# RGBNDR.net
KiCad netlist of a schematic drawn in EAGLE
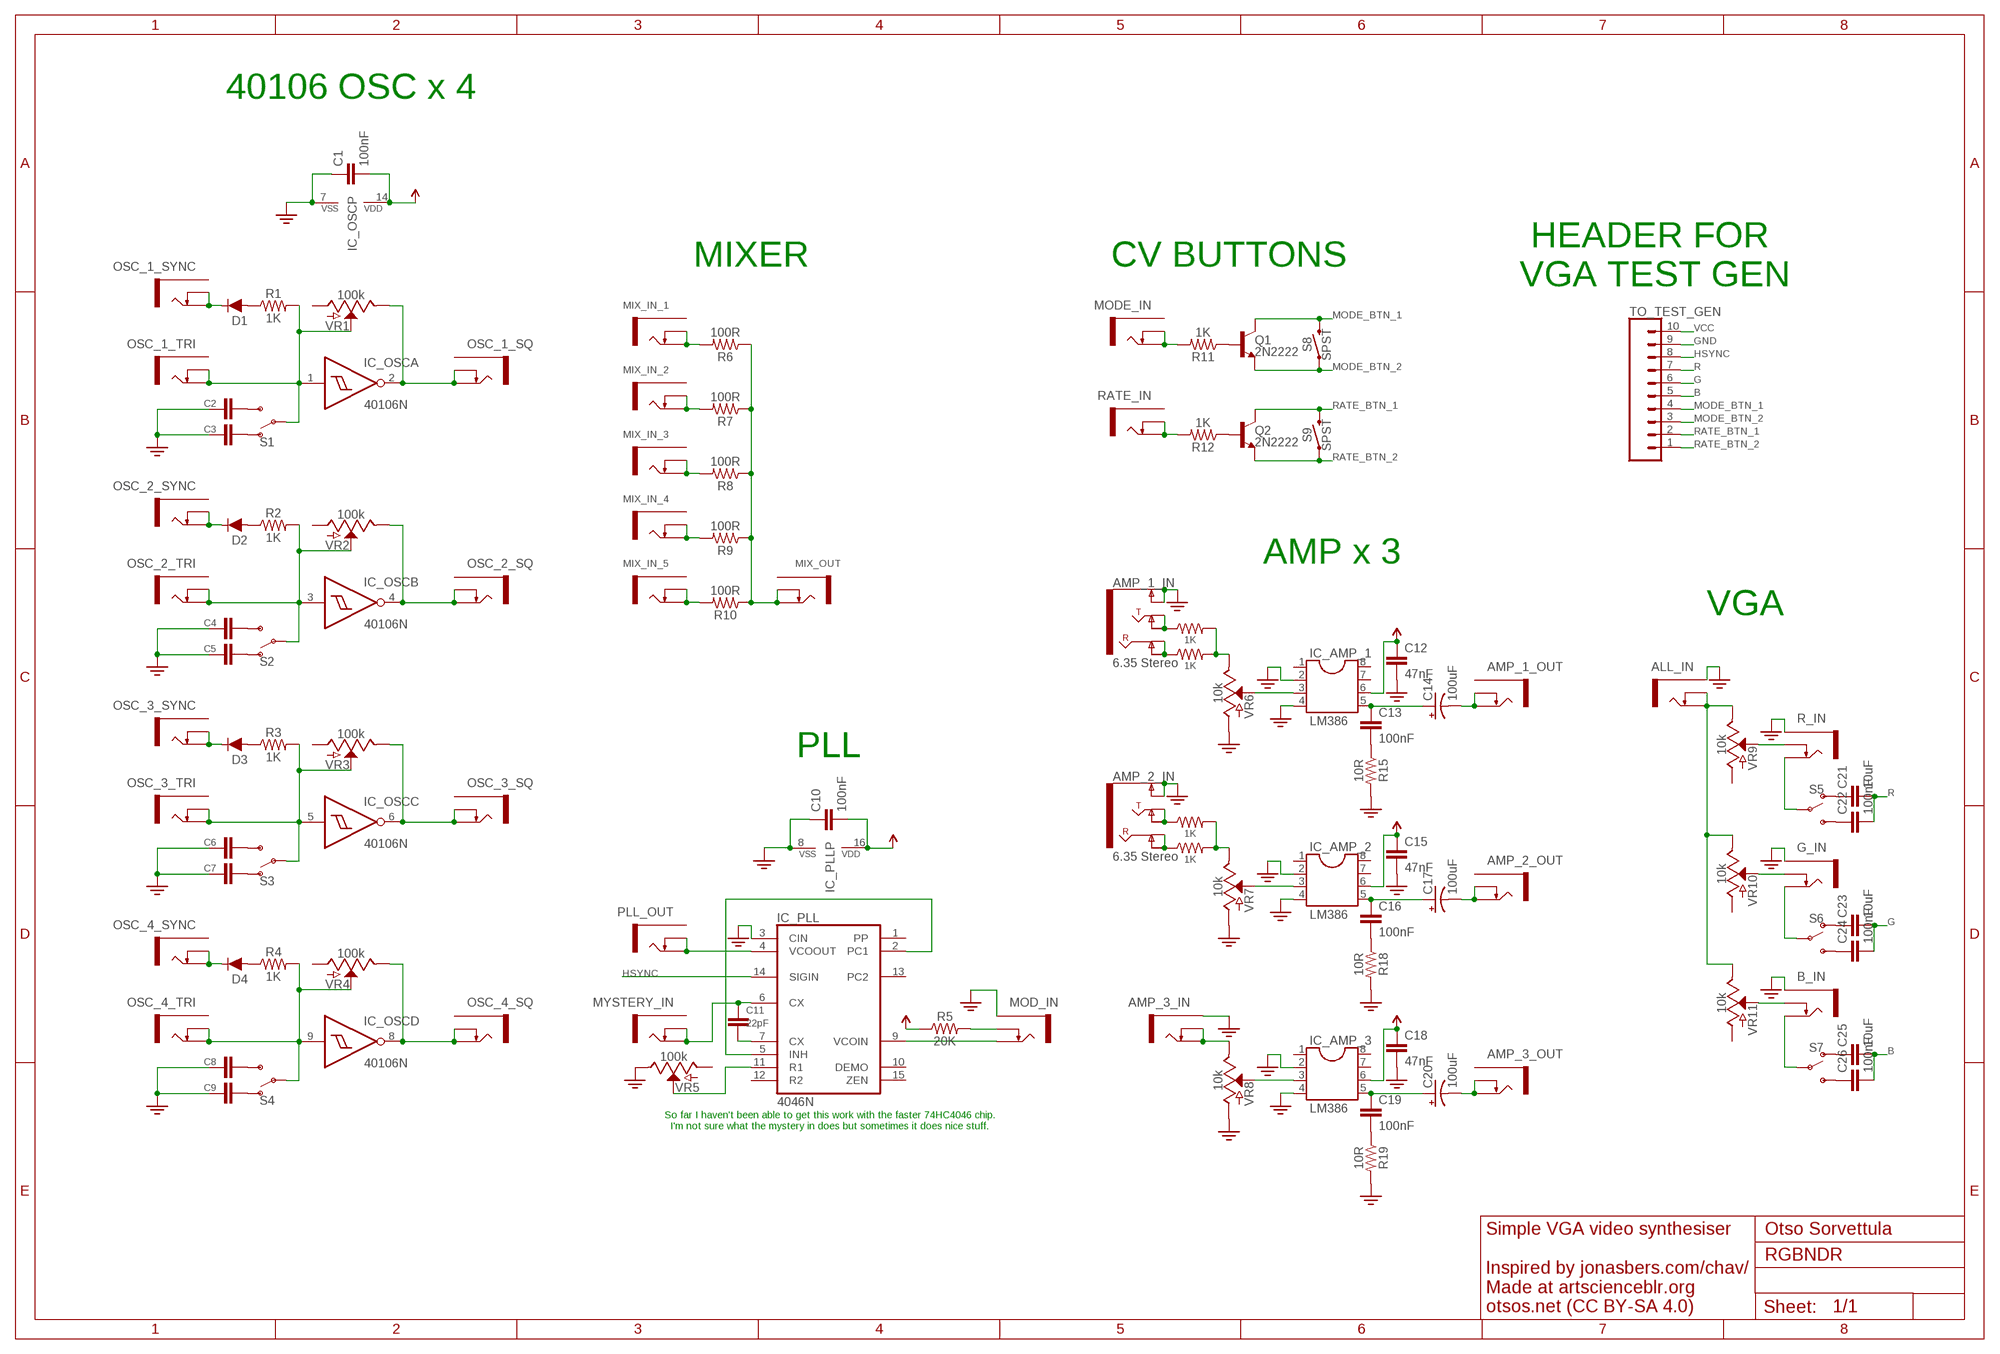
[diagram p0: schematic, sheet 1]

(export (version "E")
  (design (tool "Eeschema 10.0.6"))
  (components
    (comp (ref "ALL_IN")
      (value "WQP-PJ301M-12_JACK")
      (footprint "eagle-import:WQP-PJ301M-12_JACK")
      (libsource (lib "eagle-import") (part "WQP-PJ301M-12_JACK"))
    )
    (comp (ref "AMP_1_IN")
      (value "6.35 Stereo")
      (footprint "eagle-import:AUDIO_JACK_0.25__TRS_PTH_RA")
      (libsource (lib "eagle-import") (part "AUDIO_JACK_TRS_0.25{dblquote}_PTH_RA"))
    )
    (comp (ref "AMP_1_OUT")
      (value "WQP-PJ301M-12_JACK")
      (footprint "eagle-import:WQP-PJ301M-12_JACK")
      (libsource (lib "eagle-import") (part "WQP-PJ301M-12_JACK"))
    )
    (comp (ref "AMP_2_IN")
      (value "6.35 Stereo")
      (footprint "eagle-import:AUDIO_JACK_0.25__TRS_PTH_RA")
      (libsource (lib "eagle-import") (part "AUDIO_JACK_TRS_0.25{dblquote}_PTH_RA"))
    )
    (comp (ref "AMP_2_OUT")
      (value "WQP-PJ301M-12_JACK")
      (footprint "eagle-import:WQP-PJ301M-12_JACK")
      (libsource (lib "eagle-import") (part "WQP-PJ301M-12_JACK"))
    )
    (comp (ref "AMP_3_IN")
      (value "WQP-PJ301M-12_JACK")
      (footprint "eagle-import:WQP-PJ301M-12_JACK")
      (libsource (lib "eagle-import") (part "WQP-PJ301M-12_JACK"))
    )
    (comp (ref "AMP_3_OUT")
      (value "WQP-PJ301M-12_JACK")
      (footprint "eagle-import:WQP-PJ301M-12_JACK")
      (libsource (lib "eagle-import") (part "WQP-PJ301M-12_JACK"))
    )
    (comp (ref "B_IN")
      (value "WQP-PJ301M-12_JACK")
      (footprint "eagle-import:WQP-PJ301M-12_JACK")
      (libsource (lib "eagle-import") (part "WQP-PJ301M-12_JACK"))
    )
    (comp (ref "C1")
      (value "100nF")
      (footprint "eagle-import:CAP-PTH-SMALL-KIT")
      (libsource (lib "eagle-import") (part "0.1UF-KIT-EZ-50V-20%"))
    )
    (comp (ref "C2")
      (value "0.1UF-KIT-EZ-50V-20%")
      (footprint "eagle-import:CAP-PTH-SMALL-KIT")
      (libsource (lib "eagle-import") (part "0.1UF-KIT-EZ-50V-20%"))
    )
    (comp (ref "C3")
      (value "0.1UF-KIT-EZ-50V-20%")
      (footprint "eagle-import:CAP-PTH-SMALL-KIT")
      (libsource (lib "eagle-import") (part "0.1UF-KIT-EZ-50V-20%"))
    )
    (comp (ref "C4")
      (value "0.1UF-KIT-EZ-50V-20%")
      (footprint "eagle-import:CAP-PTH-SMALL-KIT")
      (libsource (lib "eagle-import") (part "0.1UF-KIT-EZ-50V-20%"))
    )
    (comp (ref "C5")
      (value "0.1UF-KIT-EZ-50V-20%")
      (footprint "eagle-import:CAP-PTH-SMALL-KIT")
      (libsource (lib "eagle-import") (part "0.1UF-KIT-EZ-50V-20%"))
    )
    (comp (ref "C6")
      (value "0.1UF-KIT-EZ-50V-20%")
      (footprint "eagle-import:CAP-PTH-SMALL-KIT")
      (libsource (lib "eagle-import") (part "0.1UF-KIT-EZ-50V-20%"))
    )
    (comp (ref "C7")
      (value "0.1UF-KIT-EZ-50V-20%")
      (footprint "eagle-import:CAP-PTH-SMALL-KIT")
      (libsource (lib "eagle-import") (part "0.1UF-KIT-EZ-50V-20%"))
    )
    (comp (ref "C8")
      (value "0.1UF-KIT-EZ-50V-20%")
      (footprint "eagle-import:CAP-PTH-SMALL-KIT")
      (libsource (lib "eagle-import") (part "0.1UF-KIT-EZ-50V-20%"))
    )
    (comp (ref "C9")
      (value "0.1UF-KIT-EZ-50V-20%")
      (footprint "eagle-import:CAP-PTH-SMALL-KIT")
      (libsource (lib "eagle-import") (part "0.1UF-KIT-EZ-50V-20%"))
    )
    (comp (ref "C10")
      (value "100nF")
      (footprint "eagle-import:CAP-PTH-SMALL-KIT")
      (libsource (lib "eagle-import") (part "0.1UF-KIT-EZ-50V-20%"))
    )
    (comp (ref "C11")
      (value "22pF")
      (footprint "eagle-import:CAP-PTH-2.54")
      (libsource (lib "eagle-import") (part "22PF-PTH-2.54MM-200V-5%"))
    )
    (comp (ref "C12")
      (value "47nF")
      (footprint "eagle-import:CAP-PTH-SMALL-KIT")
      (libsource (lib "eagle-import") (part "0.1UF-KIT-EZ-50V-20%"))
    )
    (comp (ref "C13")
      (value "100nF")
      (footprint "eagle-import:CAP-PTH-SMALL-KIT")
      (libsource (lib "eagle-import") (part "0.1UF-KIT-EZ-50V-20%"))
    )
    (comp (ref "C14")
      (value "100uF")
      (footprint "eagle-import:CPOL-RADIAL-2.5MM-6.5MM")
      (libsource (lib "eagle-import") (part "100UF-POLAR-RADIAL-2.5MM-25V-20%"))
    )
    (comp (ref "C15")
      (value "47nF")
      (footprint "eagle-import:CAP-PTH-SMALL-KIT")
      (libsource (lib "eagle-import") (part "0.1UF-KIT-EZ-50V-20%"))
    )
    (comp (ref "C16")
      (value "100nF")
      (footprint "eagle-import:CAP-PTH-SMALL-KIT")
      (libsource (lib "eagle-import") (part "0.1UF-KIT-EZ-50V-20%"))
    )
    (comp (ref "C17")
      (value "100uF")
      (footprint "eagle-import:CPOL-RADIAL-2.5MM-6.5MM")
      (libsource (lib "eagle-import") (part "100UF-POLAR-RADIAL-2.5MM-25V-20%"))
    )
    (comp (ref "C18")
      (value "47nF")
      (footprint "eagle-import:CAP-PTH-SMALL-KIT")
      (libsource (lib "eagle-import") (part "0.1UF-KIT-EZ-50V-20%"))
    )
    (comp (ref "C19")
      (value "100nF")
      (footprint "eagle-import:CAP-PTH-SMALL-KIT")
      (libsource (lib "eagle-import") (part "0.1UF-KIT-EZ-50V-20%"))
    )
    (comp (ref "C20")
      (value "100uF")
      (footprint "eagle-import:CPOL-RADIAL-2.5MM-6.5MM")
      (libsource (lib "eagle-import") (part "100UF-POLAR-RADIAL-2.5MM-25V-20%"))
    )
    (comp (ref "C21")
      (value "10uF")
      (footprint "eagle-import:CAP-PTH-SMALL-KIT")
      (libsource (lib "eagle-import") (part "0.1UF-KIT-EZ-50V-20%"))
    )
    (comp (ref "C22")
      (value "100nF")
      (footprint "eagle-import:CAP-PTH-SMALL-KIT")
      (libsource (lib "eagle-import") (part "0.1UF-KIT-EZ-50V-20%"))
    )
    (comp (ref "C23")
      (value "10uF")
      (footprint "eagle-import:CAP-PTH-SMALL-KIT")
      (libsource (lib "eagle-import") (part "0.1UF-KIT-EZ-50V-20%"))
    )
    (comp (ref "C24")
      (value "100nF")
      (footprint "eagle-import:CAP-PTH-SMALL-KIT")
      (libsource (lib "eagle-import") (part "0.1UF-KIT-EZ-50V-20%"))
    )
    (comp (ref "C25")
      (value "10uF")
      (footprint "eagle-import:CAP-PTH-SMALL-KIT")
      (libsource (lib "eagle-import") (part "0.1UF-KIT-EZ-50V-20%"))
    )
    (comp (ref "C26")
      (value "100nF")
      (footprint "eagle-import:CAP-PTH-SMALL-KIT")
      (libsource (lib "eagle-import") (part "0.1UF-KIT-EZ-50V-20%"))
    )
    (comp (ref "D1")
      (value "DIODE-1N4148")
      (footprint "eagle-import:DIODE-1N4148")
      (libsource (lib "eagle-import") (part "DIODE-1N4148"))
    )
    (comp (ref "D2")
      (value "DIODE-1N4148")
      (footprint "eagle-import:DIODE-1N4148")
      (libsource (lib "eagle-import") (part "DIODE-1N4148"))
    )
    (comp (ref "D3")
      (value "DIODE-1N4148")
      (footprint "eagle-import:DIODE-1N4148")
      (libsource (lib "eagle-import") (part "DIODE-1N4148"))
    )
    (comp (ref "D4")
      (value "DIODE-1N4148")
      (footprint "eagle-import:DIODE-1N4148")
      (libsource (lib "eagle-import") (part "DIODE-1N4148"))
    )
    (comp (ref "G_IN")
      (value "WQP-PJ301M-12_JACK")
      (footprint "eagle-import:WQP-PJ301M-12_JACK")
      (libsource (lib "eagle-import") (part "WQP-PJ301M-12_JACK"))
    )
    (comp (ref "IC_AMP_1")
      (value "LM386")
      (footprint "eagle-import:DIL08")
      (libsource (lib "eagle-import") (part "DIL8"))
    )
    (comp (ref "IC_AMP_2")
      (value "LM386")
      (footprint "eagle-import:DIL08")
      (libsource (lib "eagle-import") (part "DIL8"))
    )
    (comp (ref "IC_AMP_3")
      (value "LM386")
      (footprint "eagle-import:DIL08")
      (libsource (lib "eagle-import") (part "DIL8"))
    )
    (comp (ref "IC_OSC")
      (value "40106N")
      (footprint "eagle-import:DIL14")
      (libsource (lib "eagle-import") (part "40106N"))
    )
    (comp (ref "IC_PLL")
      (value "4046N")
      (footprint "eagle-import:DIL16")
      (libsource (lib "eagle-import") (part "4046N"))
    )
    (comp (ref "MIX_IN_1")
      (value "WQP-PJ301M-12_JACK")
      (footprint "eagle-import:WQP-PJ301M-12_JACK")
      (libsource (lib "eagle-import") (part "WQP-PJ301M-12_JACK"))
    )
    (comp (ref "MIX_IN_2")
      (value "WQP-PJ301M-12_JACK")
      (footprint "eagle-import:WQP-PJ301M-12_JACK")
      (libsource (lib "eagle-import") (part "WQP-PJ301M-12_JACK"))
    )
    (comp (ref "MIX_IN_3")
      (value "WQP-PJ301M-12_JACK")
      (footprint "eagle-import:WQP-PJ301M-12_JACK")
      (libsource (lib "eagle-import") (part "WQP-PJ301M-12_JACK"))
    )
    (comp (ref "MIX_IN_4")
      (value "WQP-PJ301M-12_JACK")
      (footprint "eagle-import:WQP-PJ301M-12_JACK")
      (libsource (lib "eagle-import") (part "WQP-PJ301M-12_JACK"))
    )
    (comp (ref "MIX_IN_5")
      (value "WQP-PJ301M-12_JACK")
      (footprint "eagle-import:WQP-PJ301M-12_JACK")
      (libsource (lib "eagle-import") (part "WQP-PJ301M-12_JACK"))
    )
    (comp (ref "MIX_OUT")
      (value "WQP-PJ301M-12_JACK")
      (footprint "eagle-import:WQP-PJ301M-12_JACK")
      (libsource (lib "eagle-import") (part "WQP-PJ301M-12_JACK"))
    )
    (comp (ref "MODE_IN")
      (value "WQP-PJ301M-12_JACK")
      (footprint "eagle-import:WQP-PJ301M-12_JACK")
      (libsource (lib "eagle-import") (part "WQP-PJ301M-12_JACK"))
    )
    (comp (ref "MOD_IN")
      (value "WQP-PJ301M-12_JACK")
      (footprint "eagle-import:WQP-PJ301M-12_JACK")
      (libsource (lib "eagle-import") (part "WQP-PJ301M-12_JACK"))
    )
    (comp (ref "MYSTERY_IN")
      (value "WQP-PJ301M-12_JACK")
      (footprint "eagle-import:WQP-PJ301M-12_JACK")
      (libsource (lib "eagle-import") (part "WQP-PJ301M-12_JACK"))
    )
    (comp (ref "OSC_1_SQ")
      (value "WQP-PJ301M-12_JACK")
      (footprint "eagle-import:WQP-PJ301M-12_JACK")
      (libsource (lib "eagle-import") (part "WQP-PJ301M-12_JACK"))
    )
    (comp (ref "OSC_1_SYNC")
      (value "WQP-PJ301M-12_JACK")
      (footprint "eagle-import:WQP-PJ301M-12_JACK")
      (libsource (lib "eagle-import") (part "WQP-PJ301M-12_JACK"))
    )
    (comp (ref "OSC_1_TRI")
      (value "WQP-PJ301M-12_JACK")
      (footprint "eagle-import:WQP-PJ301M-12_JACK")
      (libsource (lib "eagle-import") (part "WQP-PJ301M-12_JACK"))
    )
    (comp (ref "OSC_2_SQ")
      (value "WQP-PJ301M-12_JACK")
      (footprint "eagle-import:WQP-PJ301M-12_JACK")
      (libsource (lib "eagle-import") (part "WQP-PJ301M-12_JACK"))
    )
    (comp (ref "OSC_2_SYNC")
      (value "WQP-PJ301M-12_JACK")
      (footprint "eagle-import:WQP-PJ301M-12_JACK")
      (libsource (lib "eagle-import") (part "WQP-PJ301M-12_JACK"))
    )
    (comp (ref "OSC_2_TRI")
      (value "WQP-PJ301M-12_JACK")
      (footprint "eagle-import:WQP-PJ301M-12_JACK")
      (libsource (lib "eagle-import") (part "WQP-PJ301M-12_JACK"))
    )
    (comp (ref "OSC_3_SQ")
      (value "WQP-PJ301M-12_JACK")
      (footprint "eagle-import:WQP-PJ301M-12_JACK")
      (libsource (lib "eagle-import") (part "WQP-PJ301M-12_JACK"))
    )
    (comp (ref "OSC_3_SYNC")
      (value "WQP-PJ301M-12_JACK")
      (footprint "eagle-import:WQP-PJ301M-12_JACK")
      (libsource (lib "eagle-import") (part "WQP-PJ301M-12_JACK"))
    )
    (comp (ref "OSC_3_TRI")
      (value "WQP-PJ301M-12_JACK")
      (footprint "eagle-import:WQP-PJ301M-12_JACK")
      (libsource (lib "eagle-import") (part "WQP-PJ301M-12_JACK"))
    )
    (comp (ref "OSC_4_SQ")
      (value "WQP-PJ301M-12_JACK")
      (footprint "eagle-import:WQP-PJ301M-12_JACK")
      (libsource (lib "eagle-import") (part "WQP-PJ301M-12_JACK"))
    )
    (comp (ref "OSC_4_SYNC")
      (value "WQP-PJ301M-12_JACK")
      (footprint "eagle-import:WQP-PJ301M-12_JACK")
      (libsource (lib "eagle-import") (part "WQP-PJ301M-12_JACK"))
    )
    (comp (ref "OSC_4_TRI")
      (value "WQP-PJ301M-12_JACK")
      (footprint "eagle-import:WQP-PJ301M-12_JACK")
      (libsource (lib "eagle-import") (part "WQP-PJ301M-12_JACK"))
    )
    (comp (ref "PLL_OUT")
      (value "WQP-PJ301M-12_JACK")
      (footprint "eagle-import:WQP-PJ301M-12_JACK")
      (libsource (lib "eagle-import") (part "WQP-PJ301M-12_JACK"))
    )
    (comp (ref "Q1")
      (value "2N2222")
      (footprint "eagle-import:TO-92")
      (libsource (lib "eagle-import") (part "TRANS_NPN-P2N2222A"))
    )
    (comp (ref "Q2")
      (value "2N2222")
      (footprint "eagle-import:TO-92")
      (libsource (lib "eagle-import") (part "TRANS_NPN-P2N2222A"))
    )
    (comp (ref "R1")
      (value "1K")
      (footprint "eagle-import:AXIAL-0.3")
      (libsource (lib "eagle-import") (part "10KOHM-HORIZ-1/4W-5%"))
    )
    (comp (ref "R2")
      (value "1K")
      (footprint "eagle-import:AXIAL-0.3")
      (libsource (lib "eagle-import") (part "10KOHM-HORIZ-1/4W-5%"))
    )
    (comp (ref "R3")
      (value "1K")
      (footprint "eagle-import:AXIAL-0.3")
      (libsource (lib "eagle-import") (part "10KOHM-HORIZ-1/4W-5%"))
    )
    (comp (ref "R4")
      (value "1K")
      (footprint "eagle-import:AXIAL-0.3")
      (libsource (lib "eagle-import") (part "10KOHM-HORIZ-1/4W-5%"))
    )
    (comp (ref "R5")
      (value "20K")
      (footprint "eagle-import:AXIAL-0.3")
      (libsource (lib "eagle-import") (part "10KOHM-HORIZ-1/4W-5%"))
    )
    (comp (ref "R6")
      (value "100R")
      (footprint "eagle-import:AXIAL-0.3")
      (libsource (lib "eagle-import") (part "10KOHM-HORIZ-1/4W-5%"))
    )
    (comp (ref "R7")
      (value "100R")
      (footprint "eagle-import:AXIAL-0.3")
      (libsource (lib "eagle-import") (part "10KOHM-HORIZ-1/4W-5%"))
    )
    (comp (ref "R8")
      (value "100R")
      (footprint "eagle-import:AXIAL-0.3")
      (libsource (lib "eagle-import") (part "10KOHM-HORIZ-1/4W-5%"))
    )
    (comp (ref "R9")
      (value "100R")
      (footprint "eagle-import:AXIAL-0.3")
      (libsource (lib "eagle-import") (part "10KOHM-HORIZ-1/4W-5%"))
    )
    (comp (ref "R10")
      (value "100R")
      (footprint "eagle-import:AXIAL-0.3")
      (libsource (lib "eagle-import") (part "10KOHM-HORIZ-1/4W-5%"))
    )
    (comp (ref "R11")
      (value "1K")
      (footprint "eagle-import:AXIAL-0.3")
      (libsource (lib "eagle-import") (part "10KOHM-HORIZ-1/4W-5%"))
    )
    (comp (ref "R12")
      (value "1K")
      (footprint "eagle-import:AXIAL-0.3")
      (libsource (lib "eagle-import") (part "10KOHM-HORIZ-1/4W-5%"))
    )
    (comp (ref "R13")
      (value "1K")
      (footprint "eagle-import:AXIAL-0.3")
      (libsource (lib "eagle-import") (part "10KOHM-HORIZ-1/4W-5%"))
    )
    (comp (ref "R14")
      (value "1K")
      (footprint "eagle-import:AXIAL-0.3")
      (libsource (lib "eagle-import") (part "10KOHM-HORIZ-1/4W-5%"))
    )
    (comp (ref "R15")
      (value "10R")
      (footprint "eagle-import:AXIAL-0.3")
      (libsource (lib "eagle-import") (part "10KOHM-HORIZ-1/4W-5%"))
    )
    (comp (ref "R16")
      (value "1K")
      (footprint "eagle-import:AXIAL-0.3")
      (libsource (lib "eagle-import") (part "10KOHM-HORIZ-1/4W-5%"))
    )
    (comp (ref "R17")
      (value "1K")
      (footprint "eagle-import:AXIAL-0.3")
      (libsource (lib "eagle-import") (part "10KOHM-HORIZ-1/4W-5%"))
    )
    (comp (ref "R18")
      (value "10R")
      (footprint "eagle-import:AXIAL-0.3")
      (libsource (lib "eagle-import") (part "10KOHM-HORIZ-1/4W-5%"))
    )
    (comp (ref "R19")
      (value "10R")
      (footprint "eagle-import:AXIAL-0.3")
      (libsource (lib "eagle-import") (part "10KOHM-HORIZ-1/4W-5%"))
    )
    (comp (ref "RATE_IN")
      (value "WQP-PJ301M-12_JACK")
      (footprint "eagle-import:WQP-PJ301M-12_JACK")
      (libsource (lib "eagle-import") (part "WQP-PJ301M-12_JACK"))
    )
    (comp (ref "R_IN")
      (value "WQP-PJ301M-12_JACK")
      (footprint "eagle-import:WQP-PJ301M-12_JACK")
      (libsource (lib "eagle-import") (part "WQP-PJ301M-12_JACK"))
    )
    (comp (ref "S1")
      (value "SWITCH-SPDT-PTH-11.6X4.0MM-LOCK")
      (footprint "eagle-import:SWITCH_SPDT_PTH_11.6X4.0MM_LOCK")
      (libsource (lib "eagle-import") (part "SWITCH-SPDT-PTH-11.6X4.0MM-LOCK"))
    )
    (comp (ref "S2")
      (value "SWITCH-SPDT-PTH-11.6X4.0MM-LOCK")
      (footprint "eagle-import:SWITCH_SPDT_PTH_11.6X4.0MM_LOCK")
      (libsource (lib "eagle-import") (part "SWITCH-SPDT-PTH-11.6X4.0MM-LOCK"))
    )
    (comp (ref "S3")
      (value "SWITCH-SPDT-PTH-11.6X4.0MM-LOCK")
      (footprint "eagle-import:SWITCH_SPDT_PTH_11.6X4.0MM_LOCK")
      (libsource (lib "eagle-import") (part "SWITCH-SPDT-PTH-11.6X4.0MM-LOCK"))
    )
    (comp (ref "S4")
      (value "SWITCH-SPDT-PTH-11.6X4.0MM-LOCK")
      (footprint "eagle-import:SWITCH_SPDT_PTH_11.6X4.0MM_LOCK")
      (libsource (lib "eagle-import") (part "SWITCH-SPDT-PTH-11.6X4.0MM-LOCK"))
    )
    (comp (ref "S5")
      (value "SWITCH-SPDT-PTH-11.6X4.0MM-LOCK")
      (footprint "eagle-import:SWITCH_SPDT_PTH_11.6X4.0MM_LOCK")
      (libsource (lib "eagle-import") (part "SWITCH-SPDT-PTH-11.6X4.0MM-LOCK"))
    )
    (comp (ref "S6")
      (value "SWITCH-SPDT-PTH-11.6X4.0MM-LOCK")
      (footprint "eagle-import:SWITCH_SPDT_PTH_11.6X4.0MM_LOCK")
      (libsource (lib "eagle-import") (part "SWITCH-SPDT-PTH-11.6X4.0MM-LOCK"))
    )
    (comp (ref "S7")
      (value "SWITCH-SPDT-PTH-11.6X4.0MM-LOCK")
      (footprint "eagle-import:SWITCH_SPDT_PTH_11.6X4.0MM_LOCK")
      (libsource (lib "eagle-import") (part "SWITCH-SPDT-PTH-11.6X4.0MM-LOCK"))
    )
    (comp (ref "S8")
      (value "SPST")
      (footprint "eagle-import:TACTILE_SWITCH_PTH_6.0MM")
      (libsource (lib "eagle-import") (part "MOMENTARY-SWITCH-SPST-PTH-6.0MM"))
    )
    (comp (ref "S9")
      (value "SPST")
      (footprint "eagle-import:TACTILE_SWITCH_PTH_6.0MM")
      (libsource (lib "eagle-import") (part "MOMENTARY-SWITCH-SPST-PTH-6.0MM"))
    )
    (comp (ref "TO_TEST_GEN")
      (value "CONN_10\"")
      (footprint "eagle-import:1X10")
      (libsource (lib "eagle-import") (part "CONN_10{dblquote}"))
    )
    (comp (ref "VR1")
      (value "100k")
      (footprint "eagle-import:POT-PTH-ALPS-KIT")
      (libsource (lib "eagle-import") (part "POTENTIOMETER-PTH-9MM-1/20W-20%-KIT"))
    )
    (comp (ref "VR2")
      (value "100k")
      (footprint "eagle-import:POT-PTH-ALPS-KIT")
      (libsource (lib "eagle-import") (part "POTENTIOMETER-PTH-9MM-1/20W-20%-KIT"))
    )
    (comp (ref "VR3")
      (value "100k")
      (footprint "eagle-import:POT-PTH-ALPS-KIT")
      (libsource (lib "eagle-import") (part "POTENTIOMETER-PTH-9MM-1/20W-20%-KIT"))
    )
    (comp (ref "VR4")
      (value "100k")
      (footprint "eagle-import:POT-PTH-ALPS-KIT")
      (libsource (lib "eagle-import") (part "POTENTIOMETER-PTH-9MM-1/20W-20%-KIT"))
    )
    (comp (ref "VR5")
      (value "100k")
      (footprint "eagle-import:POT-PTH-ALPS-KIT")
      (libsource (lib "eagle-import") (part "POTENTIOMETER-PTH-9MM-1/20W-20%-KIT"))
    )
    (comp (ref "VR6")
      (value "10k")
      (footprint "eagle-import:POT-PTH-ALPS-KIT")
      (libsource (lib "eagle-import") (part "POTENTIOMETER-PTH-9MM-1/20W-20%-KIT"))
    )
    (comp (ref "VR7")
      (value "10k")
      (footprint "eagle-import:POT-PTH-ALPS-KIT")
      (libsource (lib "eagle-import") (part "POTENTIOMETER-PTH-9MM-1/20W-20%-KIT"))
    )
    (comp (ref "VR8")
      (value "10k")
      (footprint "eagle-import:POT-PTH-ALPS-KIT")
      (libsource (lib "eagle-import") (part "POTENTIOMETER-PTH-9MM-1/20W-20%-KIT"))
    )
    (comp (ref "VR9")
      (value "10k")
      (footprint "eagle-import:POT-PTH-ALPS-KIT")
      (libsource (lib "eagle-import") (part "POTENTIOMETER-PTH-9MM-1/20W-20%-KIT"))
    )
    (comp (ref "VR10")
      (value "10k")
      (footprint "eagle-import:POT-PTH-ALPS-KIT")
      (libsource (lib "eagle-import") (part "POTENTIOMETER-PTH-9MM-1/20W-20%-KIT"))
    )
    (comp (ref "VR11")
      (value "10k")
      (footprint "eagle-import:POT-PTH-ALPS-KIT")
      (libsource (lib "eagle-import") (part "POTENTIOMETER-PTH-9MM-1/20W-20%-KIT"))
    )
  )
  (nets
    (net (code "1") (name "/B") (class "Default")
      (node (ref "C25") (pin "2") (pinfunction "2_2") (pintype "passive"))
      (node (ref "C26") (pin "2") (pinfunction "2_2") (pintype "passive"))
      (node (ref "TO_TEST_GEN") (pin "5") (pinfunction "5_5") (pintype "passive"))
    )
    (net (code "2") (name "/G") (class "Default")
      (node (ref "C23") (pin "2") (pinfunction "2_2") (pintype "passive"))
      (node (ref "C24") (pin "2") (pinfunction "2_2") (pintype "passive"))
      (node (ref "TO_TEST_GEN") (pin "6") (pinfunction "6_6") (pintype "passive"))
    )
    (net (code "3") (name "/HSYNC") (class "Default")
      (node (ref "IC_PLL") (pin "14") (pinfunction "SIGIN_14") (pintype "input"))
      (node (ref "TO_TEST_GEN") (pin "8") (pinfunction "8_8") (pintype "passive"))
    )
    (net (code "4") (name "/MODE_BTN_1") (class "Default")
      (node (ref "Q1") (pin "1") (pinfunction "C_1") (pintype "passive"))
      (node (ref "S8") (pin "3") (pinfunction "2_3") (pintype "passive"))
      (node (ref "TO_TEST_GEN") (pin "4") (pinfunction "4_4") (pintype "passive"))
    )
    (net (code "5") (name "/MODE_BTN_2") (class "Default")
      (node (ref "Q1") (pin "3") (pinfunction "E_3") (pintype "passive"))
      (node (ref "S8") (pin "1") (pinfunction "1_1") (pintype "passive"))
      (node (ref "TO_TEST_GEN") (pin "3") (pinfunction "3_3") (pintype "passive"))
    )
    (net (code "6") (name "/R") (class "Default")
      (node (ref "C21") (pin "2") (pinfunction "2_2") (pintype "passive"))
      (node (ref "C22") (pin "2") (pinfunction "2_2") (pintype "passive"))
      (node (ref "TO_TEST_GEN") (pin "7") (pinfunction "7_7") (pintype "passive"))
    )
    (net (code "7") (name "/RATE_BTN_1") (class "Default")
      (node (ref "Q2") (pin "1") (pinfunction "C_1") (pintype "passive"))
      (node (ref "S9") (pin "3") (pinfunction "2_3") (pintype "passive"))
      (node (ref "TO_TEST_GEN") (pin "2") (pinfunction "2_2") (pintype "passive"))
    )
    (net (code "8") (name "/RATE_BTN_2") (class "Default")
      (node (ref "Q2") (pin "3") (pinfunction "E_3") (pintype "passive"))
      (node (ref "S9") (pin "1") (pinfunction "1_1") (pintype "passive"))
      (node (ref "TO_TEST_GEN") (pin "1") (pinfunction "1_1") (pintype "passive"))
    )
    (net (code "9") (name "GND") (class "Default")
      (node (ref "ALL_IN") (pin "P$1") (pinfunction "P$1_P$1") (pintype "passive"))
      (node (ref "AMP_1_IN") (pin "SLEEVE") (pinfunction "EARTH_SLEEVE") (pintype "bidirectional"))
      (node (ref "AMP_1_IN") (pin "SLEEVE-NORM") (pinfunction "EARTH-NORM_SLEEVE-NORM") (pintype "bidirectional"))
      (node (ref "AMP_2_IN") (pin "SLEEVE") (pinfunction "EARTH_SLEEVE") (pintype "bidirectional"))
      (node (ref "AMP_2_IN") (pin "SLEEVE-NORM") (pinfunction "EARTH-NORM_SLEEVE-NORM") (pintype "bidirectional"))
      (node (ref "AMP_3_IN") (pin "P$1") (pinfunction "P$1_P$1") (pintype "passive"))
      (node (ref "B_IN") (pin "P$1") (pinfunction "P$1_P$1") (pintype "passive"))
      (node (ref "C1") (pin "1") (pinfunction "1_1") (pintype "passive"))
      (node (ref "C10") (pin "1") (pinfunction "1_1") (pintype "passive"))
      (node (ref "C12") (pin "2") (pinfunction "2_2") (pintype "passive"))
      (node (ref "C15") (pin "2") (pinfunction "2_2") (pintype "passive"))
      (node (ref "C18") (pin "2") (pinfunction "2_2") (pintype "passive"))
      (node (ref "C2") (pin "2") (pinfunction "2_2") (pintype "passive"))
      (node (ref "C3") (pin "2") (pinfunction "2_2") (pintype "passive"))
      (node (ref "C4") (pin "2") (pinfunction "2_2") (pintype "passive"))
      (node (ref "C5") (pin "2") (pinfunction "2_2") (pintype "passive"))
      (node (ref "C6") (pin "2") (pinfunction "2_2") (pintype "passive"))
      (node (ref "C7") (pin "2") (pinfunction "2_2") (pintype "passive"))
      (node (ref "C8") (pin "2") (pinfunction "2_2") (pintype "passive"))
      (node (ref "C9") (pin "2") (pinfunction "2_2") (pintype "passive"))
      (node (ref "G_IN") (pin "P$1") (pinfunction "P$1_P$1") (pintype "passive"))
      (node (ref "IC_AMP_1") (pin "2") (pinfunction "2_2") (pintype "passive"))
      (node (ref "IC_AMP_1") (pin "4") (pinfunction "4_4") (pintype "passive"))
      (node (ref "IC_AMP_2") (pin "2") (pinfunction "2_2") (pintype "passive"))
      (node (ref "IC_AMP_2") (pin "4") (pinfunction "4_4") (pintype "passive"))
      (node (ref "IC_AMP_3") (pin "2") (pinfunction "2_2") (pintype "passive"))
      (node (ref "IC_AMP_3") (pin "4") (pinfunction "4_4") (pintype "passive"))
      (node (ref "IC_OSC") (pin "7") (pinfunction "VSS_7") (pintype "power_in"))
      (node (ref "IC_PLL") (pin "3") (pinfunction "CIN_3") (pintype "input"))
      (node (ref "IC_PLL") (pin "8") (pinfunction "VSS_8") (pintype "power_in"))
      (node (ref "MOD_IN") (pin "P$1") (pinfunction "P$1_P$1") (pintype "passive"))
      (node (ref "R15") (pin "P$2") (pinfunction "2_P$2") (pintype "passive"))
      (node (ref "R18") (pin "P$2") (pinfunction "2_P$2") (pintype "passive"))
      (node (ref "R19") (pin "P$2") (pinfunction "2_P$2") (pintype "passive"))
      (node (ref "R_IN") (pin "P$1") (pinfunction "P$1_P$1") (pintype "passive"))
      (node (ref "TO_TEST_GEN") (pin "9") (pinfunction "9_9") (pintype "passive"))
      (node (ref "VR5") (pin "P$1") (pinfunction "E_P$1") (pintype "passive"))
      (node (ref "VR6") (pin "P$3") (pinfunction "A_P$3") (pintype "passive"))
      (node (ref "VR7") (pin "P$3") (pinfunction "A_P$3") (pintype "passive"))
      (node (ref "VR8") (pin "P$3") (pinfunction "A_P$3") (pintype "passive"))
    )
    (net (code "10") (name "Net-(C11-Pad1)") (class "Default")
      (node (ref "C11") (pin "1") (pinfunction "1_1") (pintype "passive"))
      (node (ref "IC_PLL") (pin "6") (pinfunction "CX_6") (pintype "input"))
      (node (ref "MYSTERY_IN") (pin "P$2") (pinfunction "P$2_P$2") (pintype "passive"))
      (node (ref "MYSTERY_IN") (pin "P$3") (pinfunction "P$3_P$3") (pintype "passive"))
    )
    (net (code "11") (name "Net-(C11-Pad2)") (class "Default")
      (node (ref "C11") (pin "2") (pinfunction "2_2") (pintype "passive"))
      (node (ref "IC_PLL") (pin "7") (pinfunction "CX_7") (pintype "input"))
    )
    (net (code "12") (name "Net-(C14-+)") (class "Default")
      (node (ref "C13") (pin "1") (pinfunction "1_1") (pintype "passive"))
      (node (ref "C14") (pin "1") (pinfunction "+_1") (pintype "passive"))
      (node (ref "IC_AMP_1") (pin "5") (pinfunction "5_5") (pintype "passive"))
    )
    (net (code "13") (name "Net-(C14--)") (class "Default")
      (node (ref "AMP_1_OUT") (pin "P$2") (pinfunction "P$2_P$2") (pintype "passive"))
      (node (ref "AMP_1_OUT") (pin "P$3") (pinfunction "P$3_P$3") (pintype "passive"))
      (node (ref "C14") (pin "2") (pinfunction "-_2") (pintype "passive"))
    )
    (net (code "14") (name "Net-(C17-+)") (class "Default")
      (node (ref "C16") (pin "1") (pinfunction "1_1") (pintype "passive"))
      (node (ref "C17") (pin "1") (pinfunction "+_1") (pintype "passive"))
      (node (ref "IC_AMP_2") (pin "5") (pinfunction "5_5") (pintype "passive"))
    )
    (net (code "15") (name "Net-(C17--)") (class "Default")
      (node (ref "AMP_2_OUT") (pin "P$2") (pinfunction "P$2_P$2") (pintype "passive"))
      (node (ref "AMP_2_OUT") (pin "P$3") (pinfunction "P$3_P$3") (pintype "passive"))
      (node (ref "C17") (pin "2") (pinfunction "-_2") (pintype "passive"))
    )
    (net (code "16") (name "Net-(C20-+)") (class "Default")
      (node (ref "C19") (pin "1") (pinfunction "1_1") (pintype "passive"))
      (node (ref "C20") (pin "1") (pinfunction "+_1") (pintype "passive"))
      (node (ref "IC_AMP_3") (pin "5") (pinfunction "5_5") (pintype "passive"))
    )
    (net (code "17") (name "Net-(C20--)") (class "Default")
      (node (ref "AMP_3_OUT") (pin "P$2") (pinfunction "P$2_P$2") (pintype "passive"))
      (node (ref "AMP_3_OUT") (pin "P$3") (pinfunction "P$3_P$3") (pintype "passive"))
      (node (ref "C20") (pin "2") (pinfunction "-_2") (pintype "passive"))
    )
    (net (code "18") (name "Net-(D1-PadC)") (class "Default")
      (node (ref "D1") (pin "C") (pinfunction "C_C") (pintype "passive"))
      (node (ref "OSC_1_SYNC") (pin "P$2") (pinfunction "P$2_P$2") (pintype "passive"))
      (node (ref "OSC_1_SYNC") (pin "P$3") (pinfunction "P$3_P$3") (pintype "passive"))
    )
    (net (code "19") (name "Net-(D2-PadC)") (class "Default")
      (node (ref "D2") (pin "C") (pinfunction "C_C") (pintype "passive"))
      (node (ref "OSC_2_SYNC") (pin "P$2") (pinfunction "P$2_P$2") (pintype "passive"))
      (node (ref "OSC_2_SYNC") (pin "P$3") (pinfunction "P$3_P$3") (pintype "passive"))
    )
    (net (code "20") (name "Net-(D3-PadC)") (class "Default")
      (node (ref "D3") (pin "C") (pinfunction "C_C") (pintype "passive"))
      (node (ref "OSC_3_SYNC") (pin "P$2") (pinfunction "P$2_P$2") (pintype "passive"))
      (node (ref "OSC_3_SYNC") (pin "P$3") (pinfunction "P$3_P$3") (pintype "passive"))
    )
    (net (code "21") (name "Net-(D4-PadC)") (class "Default")
      (node (ref "D4") (pin "C") (pinfunction "C_C") (pintype "passive"))
      (node (ref "OSC_4_SYNC") (pin "P$2") (pinfunction "P$2_P$2") (pintype "passive"))
      (node (ref "OSC_4_SYNC") (pin "P$3") (pinfunction "P$3_P$3") (pintype "passive"))
    )
    (net (code "22") (name "Net-(IC_OSCA-I)") (class "Default")
      (node (ref "IC_OSC") (pin "1") (pinfunction "I_1") (pintype "input"))
      (node (ref "OSC_1_TRI") (pin "P$2") (pinfunction "P$2_P$2") (pintype "passive"))
      (node (ref "OSC_1_TRI") (pin "P$3") (pinfunction "P$3_P$3") (pintype "passive"))
      (node (ref "R1") (pin "P$2") (pinfunction "2_P$2") (pintype "passive"))
      (node (ref "S1") (pin "2") (pinfunction "P_2") (pintype "passive"))
      (node (ref "VR1") (pin "P$2") (pinfunction "S_P$2") (pintype "passive"))
    )
    (net (code "23") (name "Net-(IC_OSCA-O)") (class "Default")
      (node (ref "IC_OSC") (pin "2") (pinfunction "O_2") (pintype "output"))
      (node (ref "OSC_1_SQ") (pin "P$2") (pinfunction "P$2_P$2") (pintype "passive"))
      (node (ref "OSC_1_SQ") (pin "P$3") (pinfunction "P$3_P$3") (pintype "passive"))
      (node (ref "VR1") (pin "P$1") (pinfunction "E_P$1") (pintype "passive"))
    )
    (net (code "24") (name "Net-(IC_OSCB-I)") (class "Default")
      (node (ref "IC_OSC") (pin "3") (pinfunction "I_3") (pintype "input"))
      (node (ref "OSC_2_TRI") (pin "P$2") (pinfunction "P$2_P$2") (pintype "passive"))
      (node (ref "OSC_2_TRI") (pin "P$3") (pinfunction "P$3_P$3") (pintype "passive"))
      (node (ref "R2") (pin "P$2") (pinfunction "2_P$2") (pintype "passive"))
      (node (ref "S2") (pin "2") (pinfunction "P_2") (pintype "passive"))
      (node (ref "VR2") (pin "P$2") (pinfunction "S_P$2") (pintype "passive"))
    )
    (net (code "25") (name "Net-(IC_OSCB-O)") (class "Default")
      (node (ref "IC_OSC") (pin "4") (pinfunction "O_4") (pintype "output"))
      (node (ref "OSC_2_SQ") (pin "P$2") (pinfunction "P$2_P$2") (pintype "passive"))
      (node (ref "OSC_2_SQ") (pin "P$3") (pinfunction "P$3_P$3") (pintype "passive"))
      (node (ref "VR2") (pin "P$1") (pinfunction "E_P$1") (pintype "passive"))
    )
    (net (code "26") (name "Net-(IC_OSCC-I)") (class "Default")
      (node (ref "IC_OSC") (pin "5") (pinfunction "I_5") (pintype "input"))
      (node (ref "OSC_3_TRI") (pin "P$2") (pinfunction "P$2_P$2") (pintype "passive"))
      (node (ref "OSC_3_TRI") (pin "P$3") (pinfunction "P$3_P$3") (pintype "passive"))
      (node (ref "R3") (pin "P$2") (pinfunction "2_P$2") (pintype "passive"))
      (node (ref "S3") (pin "2") (pinfunction "P_2") (pintype "passive"))
      (node (ref "VR3") (pin "P$2") (pinfunction "S_P$2") (pintype "passive"))
    )
    (net (code "27") (name "Net-(IC_OSCC-O)") (class "Default")
      (node (ref "IC_OSC") (pin "6") (pinfunction "O_6") (pintype "output"))
      (node (ref "OSC_3_SQ") (pin "P$2") (pinfunction "P$2_P$2") (pintype "passive"))
      (node (ref "OSC_3_SQ") (pin "P$3") (pinfunction "P$3_P$3") (pintype "passive"))
      (node (ref "VR3") (pin "P$1") (pinfunction "E_P$1") (pintype "passive"))
    )
    (net (code "28") (name "Net-(IC_OSCD-I)") (class "Default")
      (node (ref "IC_OSC") (pin "9") (pinfunction "I_9") (pintype "input"))
      (node (ref "OSC_4_TRI") (pin "P$2") (pinfunction "P$2_P$2") (pintype "passive"))
      (node (ref "OSC_4_TRI") (pin "P$3") (pinfunction "P$3_P$3") (pintype "passive"))
      (node (ref "R4") (pin "P$2") (pinfunction "2_P$2") (pintype "passive"))
      (node (ref "S4") (pin "2") (pinfunction "P_2") (pintype "passive"))
      (node (ref "VR4") (pin "P$2") (pinfunction "S_P$2") (pintype "passive"))
    )
    (net (code "29") (name "Net-(IC_OSCD-O)") (class "Default")
      (node (ref "IC_OSC") (pin "8") (pinfunction "O_8") (pintype "output"))
      (node (ref "OSC_4_SQ") (pin "P$2") (pinfunction "P$2_P$2") (pintype "passive"))
      (node (ref "OSC_4_SQ") (pin "P$3") (pinfunction "P$3_P$3") (pintype "passive"))
      (node (ref "VR4") (pin "P$1") (pinfunction "E_P$1") (pintype "passive"))
    )
    (net (code "30") (name "Net-(IC_PLLA-INH)") (class "Default")
      (node (ref "IC_PLL") (pin "2") (pinfunction "PC1_2") (pintype "output"))
      (node (ref "IC_PLL") (pin "5") (pinfunction "INH_5") (pintype "input"))
    )
    (net (code "31") (name "Net-(IC_PLLA-R1)") (class "Default")
      (node (ref "IC_PLL") (pin "11") (pinfunction "R1_11") (pintype "input"))
      (node (ref "VR5") (pin "P$2") (pinfunction "S_P$2") (pintype "passive"))
    )
    (net (code "32") (name "Net-(IC_PLLA-VCOIN)") (class "Default")
      (node (ref "IC_PLL") (pin "9") (pinfunction "VCOIN_9") (pintype "input"))
      (node (ref "MOD_IN") (pin "P$2") (pinfunction "P$2_P$2") (pintype "passive"))
    )
    (net (code "33") (name "Net-(IC_PLLA-VCOOUT)") (class "Default")
      (node (ref "IC_PLL") (pin "4") (pinfunction "VCOOUT_4") (pintype "output"))
      (node (ref "PLL_OUT") (pin "P$2") (pinfunction "P$2_P$2") (pintype "passive"))
      (node (ref "PLL_OUT") (pin "P$3") (pinfunction "P$3_P$3") (pintype "passive"))
    )
    (net (code "34") (name "Net-(Q1-B)") (class "Default")
      (node (ref "Q1") (pin "2") (pinfunction "B_2") (pintype "passive"))
      (node (ref "R11") (pin "P$1") (pinfunction "1_P$1") (pintype "passive"))
    )
    (net (code "35") (name "Net-(Q2-B)") (class "Default")
      (node (ref "Q2") (pin "2") (pinfunction "B_2") (pintype "passive"))
      (node (ref "R12") (pin "P$1") (pinfunction "1_P$1") (pintype "passive"))
    )
    (net (code "36") (name "Net-(R1-1)") (class "Default")
      (node (ref "D1") (pin "A") (pinfunction "A_A") (pintype "passive"))
      (node (ref "R1") (pin "P$1") (pinfunction "1_P$1") (pintype "passive"))
    )
    (net (code "37") (name "Net-(R2-1)") (class "Default")
      (node (ref "D2") (pin "A") (pinfunction "A_A") (pintype "passive"))
      (node (ref "R2") (pin "P$1") (pinfunction "1_P$1") (pintype "passive"))
    )
    (net (code "38") (name "Net-(R3-1)") (class "Default")
      (node (ref "D3") (pin "A") (pinfunction "A_A") (pintype "passive"))
      (node (ref "R3") (pin "P$1") (pinfunction "1_P$1") (pintype "passive"))
    )
    (net (code "39") (name "Net-(R4-1)") (class "Default")
      (node (ref "D4") (pin "A") (pinfunction "A_A") (pintype "passive"))
      (node (ref "R4") (pin "P$1") (pinfunction "1_P$1") (pintype "passive"))
    )
    (net (code "40") (name "Net-(R5-2)") (class "Default")
      (node (ref "MOD_IN") (pin "P$3") (pinfunction "P$3_P$3") (pintype "passive"))
      (node (ref "R5") (pin "P$2") (pinfunction "2_P$2") (pintype "passive"))
    )
    (net (code "41") (name "Net-(R6-2)") (class "Default")
      (node (ref "MIX_IN_1") (pin "P$2") (pinfunction "P$2_P$2") (pintype "passive"))
      (node (ref "MIX_IN_1") (pin "P$3") (pinfunction "P$3_P$3") (pintype "passive"))
      (node (ref "R6") (pin "P$2") (pinfunction "2_P$2") (pintype "passive"))
    )
    (net (code "42") (name "Net-(R7-2)") (class "Default")
      (node (ref "MIX_IN_2") (pin "P$2") (pinfunction "P$2_P$2") (pintype "passive"))
      (node (ref "MIX_IN_2") (pin "P$3") (pinfunction "P$3_P$3") (pintype "passive"))
      (node (ref "R7") (pin "P$2") (pinfunction "2_P$2") (pintype "passive"))
    )
    (net (code "43") (name "Net-(R8-2)") (class "Default")
      (node (ref "MIX_IN_3") (pin "P$2") (pinfunction "P$2_P$2") (pintype "passive"))
      (node (ref "MIX_IN_3") (pin "P$3") (pinfunction "P$3_P$3") (pintype "passive"))
      (node (ref "R8") (pin "P$2") (pinfunction "2_P$2") (pintype "passive"))
    )
    (net (code "44") (name "Net-(R9-2)") (class "Default")
      (node (ref "MIX_IN_4") (pin "P$2") (pinfunction "P$2_P$2") (pintype "passive"))
      (node (ref "MIX_IN_4") (pin "P$3") (pinfunction "P$3_P$3") (pintype "passive"))
      (node (ref "R9") (pin "P$2") (pinfunction "2_P$2") (pintype "passive"))
    )
    (net (code "45") (name "Net-(R10-1)") (class "Default")
      (node (ref "MIX_OUT") (pin "P$2") (pinfunction "P$2_P$2") (pintype "passive"))
      (node (ref "MIX_OUT") (pin "P$3") (pinfunction "P$3_P$3") (pintype "passive"))
      (node (ref "R10") (pin "P$1") (pinfunction "1_P$1") (pintype "passive"))
      (node (ref "R6") (pin "P$1") (pinfunction "1_P$1") (pintype "passive"))
      (node (ref "R7") (pin "P$1") (pinfunction "1_P$1") (pintype "passive"))
      (node (ref "R8") (pin "P$1") (pinfunction "1_P$1") (pintype "passive"))
      (node (ref "R9") (pin "P$1") (pinfunction "1_P$1") (pintype "passive"))
    )
    (net (code "46") (name "Net-(R10-2)") (class "Default")
      (node (ref "MIX_IN_5") (pin "P$2") (pinfunction "P$2_P$2") (pintype "passive"))
      (node (ref "MIX_IN_5") (pin "P$3") (pinfunction "P$3_P$3") (pintype "passive"))
      (node (ref "R10") (pin "P$2") (pinfunction "2_P$2") (pintype "passive"))
    )
    (net (code "47") (name "Net-(R11-2)") (class "Default")
      (node (ref "MODE_IN") (pin "P$2") (pinfunction "P$2_P$2") (pintype "passive"))
      (node (ref "MODE_IN") (pin "P$3") (pinfunction "P$3_P$3") (pintype "passive"))
      (node (ref "R11") (pin "P$2") (pinfunction "2_P$2") (pintype "passive"))
    )
    (net (code "48") (name "Net-(R12-2)") (class "Default")
      (node (ref "R12") (pin "P$2") (pinfunction "2_P$2") (pintype "passive"))
      (node (ref "RATE_IN") (pin "P$2") (pinfunction "P$2_P$2") (pintype "passive"))
      (node (ref "RATE_IN") (pin "P$3") (pinfunction "P$3_P$3") (pintype "passive"))
    )
    (net (code "49") (name "Net-(R13-1)") (class "Default")
      (node (ref "AMP_1_IN") (pin "TIP") (pinfunction "TIP_TIP") (pintype "bidirectional"))
      (node (ref "AMP_1_IN") (pin "TIP-NORM") (pinfunction "TIP-NORM_TIP-NORM") (pintype "bidirectional"))
      (node (ref "R13") (pin "P$1") (pinfunction "1_P$1") (pintype "passive"))
    )
    (net (code "50") (name "Net-(R13-2)") (class "Default")
      (node (ref "R13") (pin "P$2") (pinfunction "2_P$2") (pintype "passive"))
      (node (ref "R14") (pin "P$2") (pinfunction "2_P$2") (pintype "passive"))
      (node (ref "VR6") (pin "P$1") (pinfunction "E_P$1") (pintype "passive"))
    )
    (net (code "51") (name "Net-(R14-1)") (class "Default")
      (node (ref "AMP_1_IN") (pin "RING") (pinfunction "RING_RING") (pintype "bidirectional"))
      (node (ref "AMP_1_IN") (pin "RING-NORM") (pinfunction "RING-NORM_RING-NORM") (pintype "bidirectional"))
      (node (ref "R14") (pin "P$1") (pinfunction "1_P$1") (pintype "passive"))
    )
    (net (code "52") (name "Net-(R15-1)") (class "Default")
      (node (ref "C13") (pin "2") (pinfunction "2_2") (pintype "passive"))
      (node (ref "R15") (pin "P$1") (pinfunction "1_P$1") (pintype "passive"))
    )
    (net (code "53") (name "Net-(R16-1)") (class "Default")
      (node (ref "AMP_2_IN") (pin "TIP") (pinfunction "TIP_TIP") (pintype "bidirectional"))
      (node (ref "AMP_2_IN") (pin "TIP-NORM") (pinfunction "TIP-NORM_TIP-NORM") (pintype "bidirectional"))
      (node (ref "R16") (pin "P$1") (pinfunction "1_P$1") (pintype "passive"))
    )
    (net (code "54") (name "Net-(R16-2)") (class "Default")
      (node (ref "R16") (pin "P$2") (pinfunction "2_P$2") (pintype "passive"))
      (node (ref "R17") (pin "P$2") (pinfunction "2_P$2") (pintype "passive"))
      (node (ref "VR7") (pin "P$1") (pinfunction "E_P$1") (pintype "passive"))
    )
    (net (code "55") (name "Net-(R17-1)") (class "Default")
      (node (ref "AMP_2_IN") (pin "RING") (pinfunction "RING_RING") (pintype "bidirectional"))
      (node (ref "AMP_2_IN") (pin "RING-NORM") (pinfunction "RING-NORM_RING-NORM") (pintype "bidirectional"))
      (node (ref "R17") (pin "P$1") (pinfunction "1_P$1") (pintype "passive"))
    )
    (net (code "56") (name "Net-(R18-1)") (class "Default")
      (node (ref "C16") (pin "2") (pinfunction "2_2") (pintype "passive"))
      (node (ref "R18") (pin "P$1") (pinfunction "1_P$1") (pintype "passive"))
    )
    (net (code "57") (name "Net-(R19-1)") (class "Default")
      (node (ref "C19") (pin "2") (pinfunction "2_2") (pintype "passive"))
      (node (ref "R19") (pin "P$1") (pinfunction "1_P$1") (pintype "passive"))
    )
    (net (code "58") (name "Net-(S1-O)") (class "Default")
      (node (ref "C3") (pin "1") (pinfunction "1_1") (pintype "passive"))
      (node (ref "S1") (pin "1") (pinfunction "O_1") (pintype "passive"))
    )
    (net (code "59") (name "Net-(S1-S)") (class "Default")
      (node (ref "C2") (pin "1") (pinfunction "1_1") (pintype "passive"))
      (node (ref "S1") (pin "3") (pinfunction "S_3") (pintype "passive"))
    )
    (net (code "60") (name "Net-(S2-O)") (class "Default")
      (node (ref "C5") (pin "1") (pinfunction "1_1") (pintype "passive"))
      (node (ref "S2") (pin "1") (pinfunction "O_1") (pintype "passive"))
    )
    (net (code "61") (name "Net-(S2-S)") (class "Default")
      (node (ref "C4") (pin "1") (pinfunction "1_1") (pintype "passive"))
      (node (ref "S2") (pin "3") (pinfunction "S_3") (pintype "passive"))
    )
    (net (code "62") (name "Net-(S3-O)") (class "Default")
      (node (ref "C7") (pin "1") (pinfunction "1_1") (pintype "passive"))
      (node (ref "S3") (pin "1") (pinfunction "O_1") (pintype "passive"))
    )
    (net (code "63") (name "Net-(S3-S)") (class "Default")
      (node (ref "C6") (pin "1") (pinfunction "1_1") (pintype "passive"))
      (node (ref "S3") (pin "3") (pinfunction "S_3") (pintype "passive"))
    )
    (net (code "64") (name "Net-(S4-O)") (class "Default")
      (node (ref "C9") (pin "1") (pinfunction "1_1") (pintype "passive"))
      (node (ref "S4") (pin "1") (pinfunction "O_1") (pintype "passive"))
    )
    (net (code "65") (name "Net-(S4-S)") (class "Default")
      (node (ref "C8") (pin "1") (pinfunction "1_1") (pintype "passive"))
      (node (ref "S4") (pin "3") (pinfunction "S_3") (pintype "passive"))
    )
    (net (code "66") (name "Net-(S5-O)") (class "Default")
      (node (ref "C21") (pin "1") (pinfunction "1_1") (pintype "passive"))
      (node (ref "S5") (pin "1") (pinfunction "O_1") (pintype "passive"))
    )
    (net (code "67") (name "Net-(S5-P)") (class "Default")
      (node (ref "R_IN") (pin "P$2") (pinfunction "P$2_P$2") (pintype "passive"))
      (node (ref "S5") (pin "2") (pinfunction "P_2") (pintype "passive"))
    )
    (net (code "68") (name "Net-(S5-S)") (class "Default")
      (node (ref "C22") (pin "1") (pinfunction "1_1") (pintype "passive"))
      (node (ref "S5") (pin "3") (pinfunction "S_3") (pintype "passive"))
    )
    (net (code "69") (name "Net-(S6-O)") (class "Default")
      (node (ref "C23") (pin "1") (pinfunction "1_1") (pintype "passive"))
      (node (ref "S6") (pin "1") (pinfunction "O_1") (pintype "passive"))
    )
    (net (code "70") (name "Net-(S6-P)") (class "Default")
      (node (ref "G_IN") (pin "P$2") (pinfunction "P$2_P$2") (pintype "passive"))
      (node (ref "S6") (pin "2") (pinfunction "P_2") (pintype "passive"))
    )
    (net (code "71") (name "Net-(S6-S)") (class "Default")
      (node (ref "C24") (pin "1") (pinfunction "1_1") (pintype "passive"))
      (node (ref "S6") (pin "3") (pinfunction "S_3") (pintype "passive"))
    )
    (net (code "72") (name "Net-(S7-O)") (class "Default")
      (node (ref "C25") (pin "1") (pinfunction "1_1") (pintype "passive"))
      (node (ref "S7") (pin "1") (pinfunction "O_1") (pintype "passive"))
    )
    (net (code "73") (name "Net-(S7-P)") (class "Default")
      (node (ref "B_IN") (pin "P$2") (pinfunction "P$2_P$2") (pintype "passive"))
      (node (ref "S7") (pin "2") (pinfunction "P_2") (pintype "passive"))
    )
    (net (code "74") (name "Net-(S7-S)") (class "Default")
      (node (ref "C26") (pin "1") (pinfunction "1_1") (pintype "passive"))
      (node (ref "S7") (pin "3") (pinfunction "S_3") (pintype "passive"))
    )
    (net (code "75") (name "Net-(VR6-S)") (class "Default")
      (node (ref "IC_AMP_1") (pin "3") (pinfunction "3_3") (pintype "passive"))
      (node (ref "VR6") (pin "P$2") (pinfunction "S_P$2") (pintype "passive"))
    )
    (net (code "76") (name "Net-(VR7-S)") (class "Default")
      (node (ref "IC_AMP_2") (pin "3") (pinfunction "3_3") (pintype "passive"))
      (node (ref "VR7") (pin "P$2") (pinfunction "S_P$2") (pintype "passive"))
    )
    (net (code "77") (name "Net-(VR8-E)") (class "Default")
      (node (ref "AMP_3_IN") (pin "P$2") (pinfunction "P$2_P$2") (pintype "passive"))
      (node (ref "AMP_3_IN") (pin "P$3") (pinfunction "P$3_P$3") (pintype "passive"))
      (node (ref "VR8") (pin "P$1") (pinfunction "E_P$1") (pintype "passive"))
    )
    (net (code "78") (name "Net-(VR8-S)") (class "Default")
      (node (ref "IC_AMP_3") (pin "3") (pinfunction "3_3") (pintype "passive"))
      (node (ref "VR8") (pin "P$2") (pinfunction "S_P$2") (pintype "passive"))
    )
    (net (code "79") (name "Net-(VR9-S)") (class "Default")
      (node (ref "R_IN") (pin "P$3") (pinfunction "P$3_P$3") (pintype "passive"))
      (node (ref "VR9") (pin "P$2") (pinfunction "S_P$2") (pintype "passive"))
    )
    (net (code "80") (name "Net-(VR10-E)") (class "Default")
      (node (ref "ALL_IN") (pin "P$2") (pinfunction "P$2_P$2") (pintype "passive"))
      (node (ref "ALL_IN") (pin "P$3") (pinfunction "P$3_P$3") (pintype "passive"))
      (node (ref "VR10") (pin "P$1") (pinfunction "E_P$1") (pintype "passive"))
      (node (ref "VR11") (pin "P$1") (pinfunction "E_P$1") (pintype "passive"))
      (node (ref "VR9") (pin "P$1") (pinfunction "E_P$1") (pintype "passive"))
    )
    (net (code "81") (name "Net-(VR10-S)") (class "Default")
      (node (ref "G_IN") (pin "P$3") (pinfunction "P$3_P$3") (pintype "passive"))
      (node (ref "VR10") (pin "P$2") (pinfunction "S_P$2") (pintype "passive"))
    )
    (net (code "82") (name "Net-(VR11-S)") (class "Default")
      (node (ref "B_IN") (pin "P$3") (pinfunction "P$3_P$3") (pintype "passive"))
      (node (ref "VR11") (pin "P$2") (pinfunction "S_P$2") (pintype "passive"))
    )
    (net (code "83") (name "VCC") (class "Default")
      (node (ref "C1") (pin "2") (pinfunction "2_2") (pintype "passive"))
      (node (ref "C10") (pin "2") (pinfunction "2_2") (pintype "passive"))
      (node (ref "C12") (pin "1") (pinfunction "1_1") (pintype "passive"))
      (node (ref "C15") (pin "1") (pinfunction "1_1") (pintype "passive"))
      (node (ref "C18") (pin "1") (pinfunction "1_1") (pintype "passive"))
      (node (ref "IC_AMP_1") (pin "6") (pinfunction "6_6") (pintype "passive"))
      (node (ref "IC_AMP_2") (pin "6") (pinfunction "6_6") (pintype "passive"))
      (node (ref "IC_AMP_3") (pin "6") (pinfunction "6_6") (pintype "passive"))
      (node (ref "IC_OSC") (pin "14") (pinfunction "VDD_14") (pintype "power_in"))
      (node (ref "IC_PLL") (pin "16") (pinfunction "VDD_16") (pintype "power_in"))
      (node (ref "R5") (pin "P$1") (pinfunction "1_P$1") (pintype "passive"))
      (node (ref "TO_TEST_GEN") (pin "10") (pinfunction "10_10") (pintype "passive"))
    )
    (net (code "84") (name "unconnected-(AMP_1_OUT-PadP$1)") (class "Default")
      (node (ref "AMP_1_OUT") (pin "P$1") (pinfunction "P$1_P$1") (pintype "passive"))
    )
    (net (code "85") (name "unconnected-(AMP_2_OUT-PadP$1)") (class "Default")
      (node (ref "AMP_2_OUT") (pin "P$1") (pinfunction "P$1_P$1") (pintype "passive"))
    )
    (net (code "86") (name "unconnected-(AMP_3_OUT-PadP$1)") (class "Default")
      (node (ref "AMP_3_OUT") (pin "P$1") (pinfunction "P$1_P$1") (pintype "passive"))
    )
    (net (code "87") (name "unconnected-(IC_AMP_1-Pad1)") (class "Default")
      (node (ref "IC_AMP_1") (pin "1") (pinfunction "1_1") (pintype "passive"))
    )
    (net (code "88") (name "unconnected-(IC_AMP_1-Pad7)") (class "Default")
      (node (ref "IC_AMP_1") (pin "7") (pinfunction "7_7") (pintype "passive"))
    )
    (net (code "89") (name "unconnected-(IC_AMP_1-Pad8)") (class "Default")
      (node (ref "IC_AMP_1") (pin "8") (pinfunction "8_8") (pintype "passive"))
    )
    (net (code "90") (name "unconnected-(IC_AMP_2-Pad1)") (class "Default")
      (node (ref "IC_AMP_2") (pin "1") (pinfunction "1_1") (pintype "passive"))
    )
    (net (code "91") (name "unconnected-(IC_AMP_2-Pad7)") (class "Default")
      (node (ref "IC_AMP_2") (pin "7") (pinfunction "7_7") (pintype "passive"))
    )
    (net (code "92") (name "unconnected-(IC_AMP_2-Pad8)") (class "Default")
      (node (ref "IC_AMP_2") (pin "8") (pinfunction "8_8") (pintype "passive"))
    )
    (net (code "93") (name "unconnected-(IC_AMP_3-Pad1)") (class "Default")
      (node (ref "IC_AMP_3") (pin "1") (pinfunction "1_1") (pintype "passive"))
    )
    (net (code "94") (name "unconnected-(IC_AMP_3-Pad7)") (class "Default")
      (node (ref "IC_AMP_3") (pin "7") (pinfunction "7_7") (pintype "passive"))
    )
    (net (code "95") (name "unconnected-(IC_AMP_3-Pad8)") (class "Default")
      (node (ref "IC_AMP_3") (pin "8") (pinfunction "8_8") (pintype "passive"))
    )
    (net (code "96") (name "unconnected-(IC_PLLA-DEMO-Pad10)") (class "Default")
      (node (ref "IC_PLL") (pin "10") (pinfunction "DEMO_10") (pintype "output"))
    )
    (net (code "97") (name "unconnected-(IC_PLLA-PC2-Pad13)") (class "Default")
      (node (ref "IC_PLL") (pin "13") (pinfunction "PC2_13") (pintype "output"))
    )
    (net (code "98") (name "unconnected-(IC_PLLA-PP-Pad1)") (class "Default")
      (node (ref "IC_PLL") (pin "1") (pinfunction "PP_1") (pintype "output"))
    )
    (net (code "99") (name "unconnected-(IC_PLLA-R2-Pad12)") (class "Default")
      (node (ref "IC_PLL") (pin "12") (pinfunction "R2_12") (pintype "input"))
    )
    (net (code "100") (name "unconnected-(IC_PLLA-ZEN-Pad15)") (class "Default")
      (node (ref "IC_PLL") (pin "15") (pinfunction "ZEN_15") (pintype "input"))
    )
    (net (code "101") (name "unconnected-(MIX_IN_1-PadP$1)") (class "Default")
      (node (ref "MIX_IN_1") (pin "P$1") (pinfunction "P$1_P$1") (pintype "passive"))
    )
    (net (code "102") (name "unconnected-(MIX_IN_2-PadP$1)") (class "Default")
      (node (ref "MIX_IN_2") (pin "P$1") (pinfunction "P$1_P$1") (pintype "passive"))
    )
    (net (code "103") (name "unconnected-(MIX_IN_3-PadP$1)") (class "Default")
      (node (ref "MIX_IN_3") (pin "P$1") (pinfunction "P$1_P$1") (pintype "passive"))
    )
    (net (code "104") (name "unconnected-(MIX_IN_4-PadP$1)") (class "Default")
      (node (ref "MIX_IN_4") (pin "P$1") (pinfunction "P$1_P$1") (pintype "passive"))
    )
    (net (code "105") (name "unconnected-(MIX_IN_5-PadP$1)") (class "Default")
      (node (ref "MIX_IN_5") (pin "P$1") (pinfunction "P$1_P$1") (pintype "passive"))
    )
    (net (code "106") (name "unconnected-(MIX_OUT-PadP$1)") (class "Default")
      (node (ref "MIX_OUT") (pin "P$1") (pinfunction "P$1_P$1") (pintype "passive"))
    )
    (net (code "107") (name "unconnected-(MODE_IN-PadP$1)") (class "Default")
      (node (ref "MODE_IN") (pin "P$1") (pinfunction "P$1_P$1") (pintype "passive"))
    )
    (net (code "108") (name "unconnected-(MYSTERY_IN-PadP$1)") (class "Default")
      (node (ref "MYSTERY_IN") (pin "P$1") (pinfunction "P$1_P$1") (pintype "passive"))
    )
    (net (code "109") (name "unconnected-(OSC_1_SQ-PadP$1)") (class "Default")
      (node (ref "OSC_1_SQ") (pin "P$1") (pinfunction "P$1_P$1") (pintype "passive"))
    )
    (net (code "110") (name "unconnected-(OSC_1_SYNC-PadP$1)") (class "Default")
      (node (ref "OSC_1_SYNC") (pin "P$1") (pinfunction "P$1_P$1") (pintype "passive"))
    )
    (net (code "111") (name "unconnected-(OSC_1_TRI-PadP$1)") (class "Default")
      (node (ref "OSC_1_TRI") (pin "P$1") (pinfunction "P$1_P$1") (pintype "passive"))
    )
    (net (code "112") (name "unconnected-(OSC_2_SQ-PadP$1)") (class "Default")
      (node (ref "OSC_2_SQ") (pin "P$1") (pinfunction "P$1_P$1") (pintype "passive"))
    )
    (net (code "113") (name "unconnected-(OSC_2_SYNC-PadP$1)") (class "Default")
      (node (ref "OSC_2_SYNC") (pin "P$1") (pinfunction "P$1_P$1") (pintype "passive"))
    )
    (net (code "114") (name "unconnected-(OSC_2_TRI-PadP$1)") (class "Default")
      (node (ref "OSC_2_TRI") (pin "P$1") (pinfunction "P$1_P$1") (pintype "passive"))
    )
    (net (code "115") (name "unconnected-(OSC_3_SQ-PadP$1)") (class "Default")
      (node (ref "OSC_3_SQ") (pin "P$1") (pinfunction "P$1_P$1") (pintype "passive"))
    )
    (net (code "116") (name "unconnected-(OSC_3_SYNC-PadP$1)") (class "Default")
      (node (ref "OSC_3_SYNC") (pin "P$1") (pinfunction "P$1_P$1") (pintype "passive"))
    )
    (net (code "117") (name "unconnected-(OSC_3_TRI-PadP$1)") (class "Default")
      (node (ref "OSC_3_TRI") (pin "P$1") (pinfunction "P$1_P$1") (pintype "passive"))
    )
    (net (code "118") (name "unconnected-(OSC_4_SQ-PadP$1)") (class "Default")
      (node (ref "OSC_4_SQ") (pin "P$1") (pinfunction "P$1_P$1") (pintype "passive"))
    )
    (net (code "119") (name "unconnected-(OSC_4_SYNC-PadP$1)") (class "Default")
      (node (ref "OSC_4_SYNC") (pin "P$1") (pinfunction "P$1_P$1") (pintype "passive"))
    )
    (net (code "120") (name "unconnected-(OSC_4_TRI-PadP$1)") (class "Default")
      (node (ref "OSC_4_TRI") (pin "P$1") (pinfunction "P$1_P$1") (pintype "passive"))
    )
    (net (code "121") (name "unconnected-(PLL_OUT-PadP$1)") (class "Default")
      (node (ref "PLL_OUT") (pin "P$1") (pinfunction "P$1_P$1") (pintype "passive"))
    )
    (net (code "122") (name "unconnected-(RATE_IN-PadP$1)") (class "Default")
      (node (ref "RATE_IN") (pin "P$1") (pinfunction "P$1_P$1") (pintype "passive"))
    )
    (net (code "123") (name "unconnected-(VR1-A-PadP$3)") (class "Default")
      (node (ref "VR1") (pin "P$3") (pinfunction "A_P$3") (pintype "passive"))
    )
    (net (code "124") (name "unconnected-(VR2-A-PadP$3)") (class "Default")
      (node (ref "VR2") (pin "P$3") (pinfunction "A_P$3") (pintype "passive"))
    )
    (net (code "125") (name "unconnected-(VR3-A-PadP$3)") (class "Default")
      (node (ref "VR3") (pin "P$3") (pinfunction "A_P$3") (pintype "passive"))
    )
    (net (code "126") (name "unconnected-(VR4-A-PadP$3)") (class "Default")
      (node (ref "VR4") (pin "P$3") (pinfunction "A_P$3") (pintype "passive"))
    )
    (net (code "127") (name "unconnected-(VR5-A-PadP$3)") (class "Default")
      (node (ref "VR5") (pin "P$3") (pinfunction "A_P$3") (pintype "passive"))
    )
    (net (code "128") (name "unconnected-(VR9-A-PadP$3)") (class "Default")
      (node (ref "VR9") (pin "P$3") (pinfunction "A_P$3") (pintype "passive"))
    )
    (net (code "129") (name "unconnected-(VR10-A-PadP$3)") (class "Default")
      (node (ref "VR10") (pin "P$3") (pinfunction "A_P$3") (pintype "passive"))
    )
    (net (code "130") (name "unconnected-(VR11-A-PadP$3)") (class "Default")
      (node (ref "VR11") (pin "P$3") (pinfunction "A_P$3") (pintype "passive"))
    )
  )
)
